# mLRS-tx-dualE22-top-v031.net
KiCad netlist of a schematic drawn in EAGLE
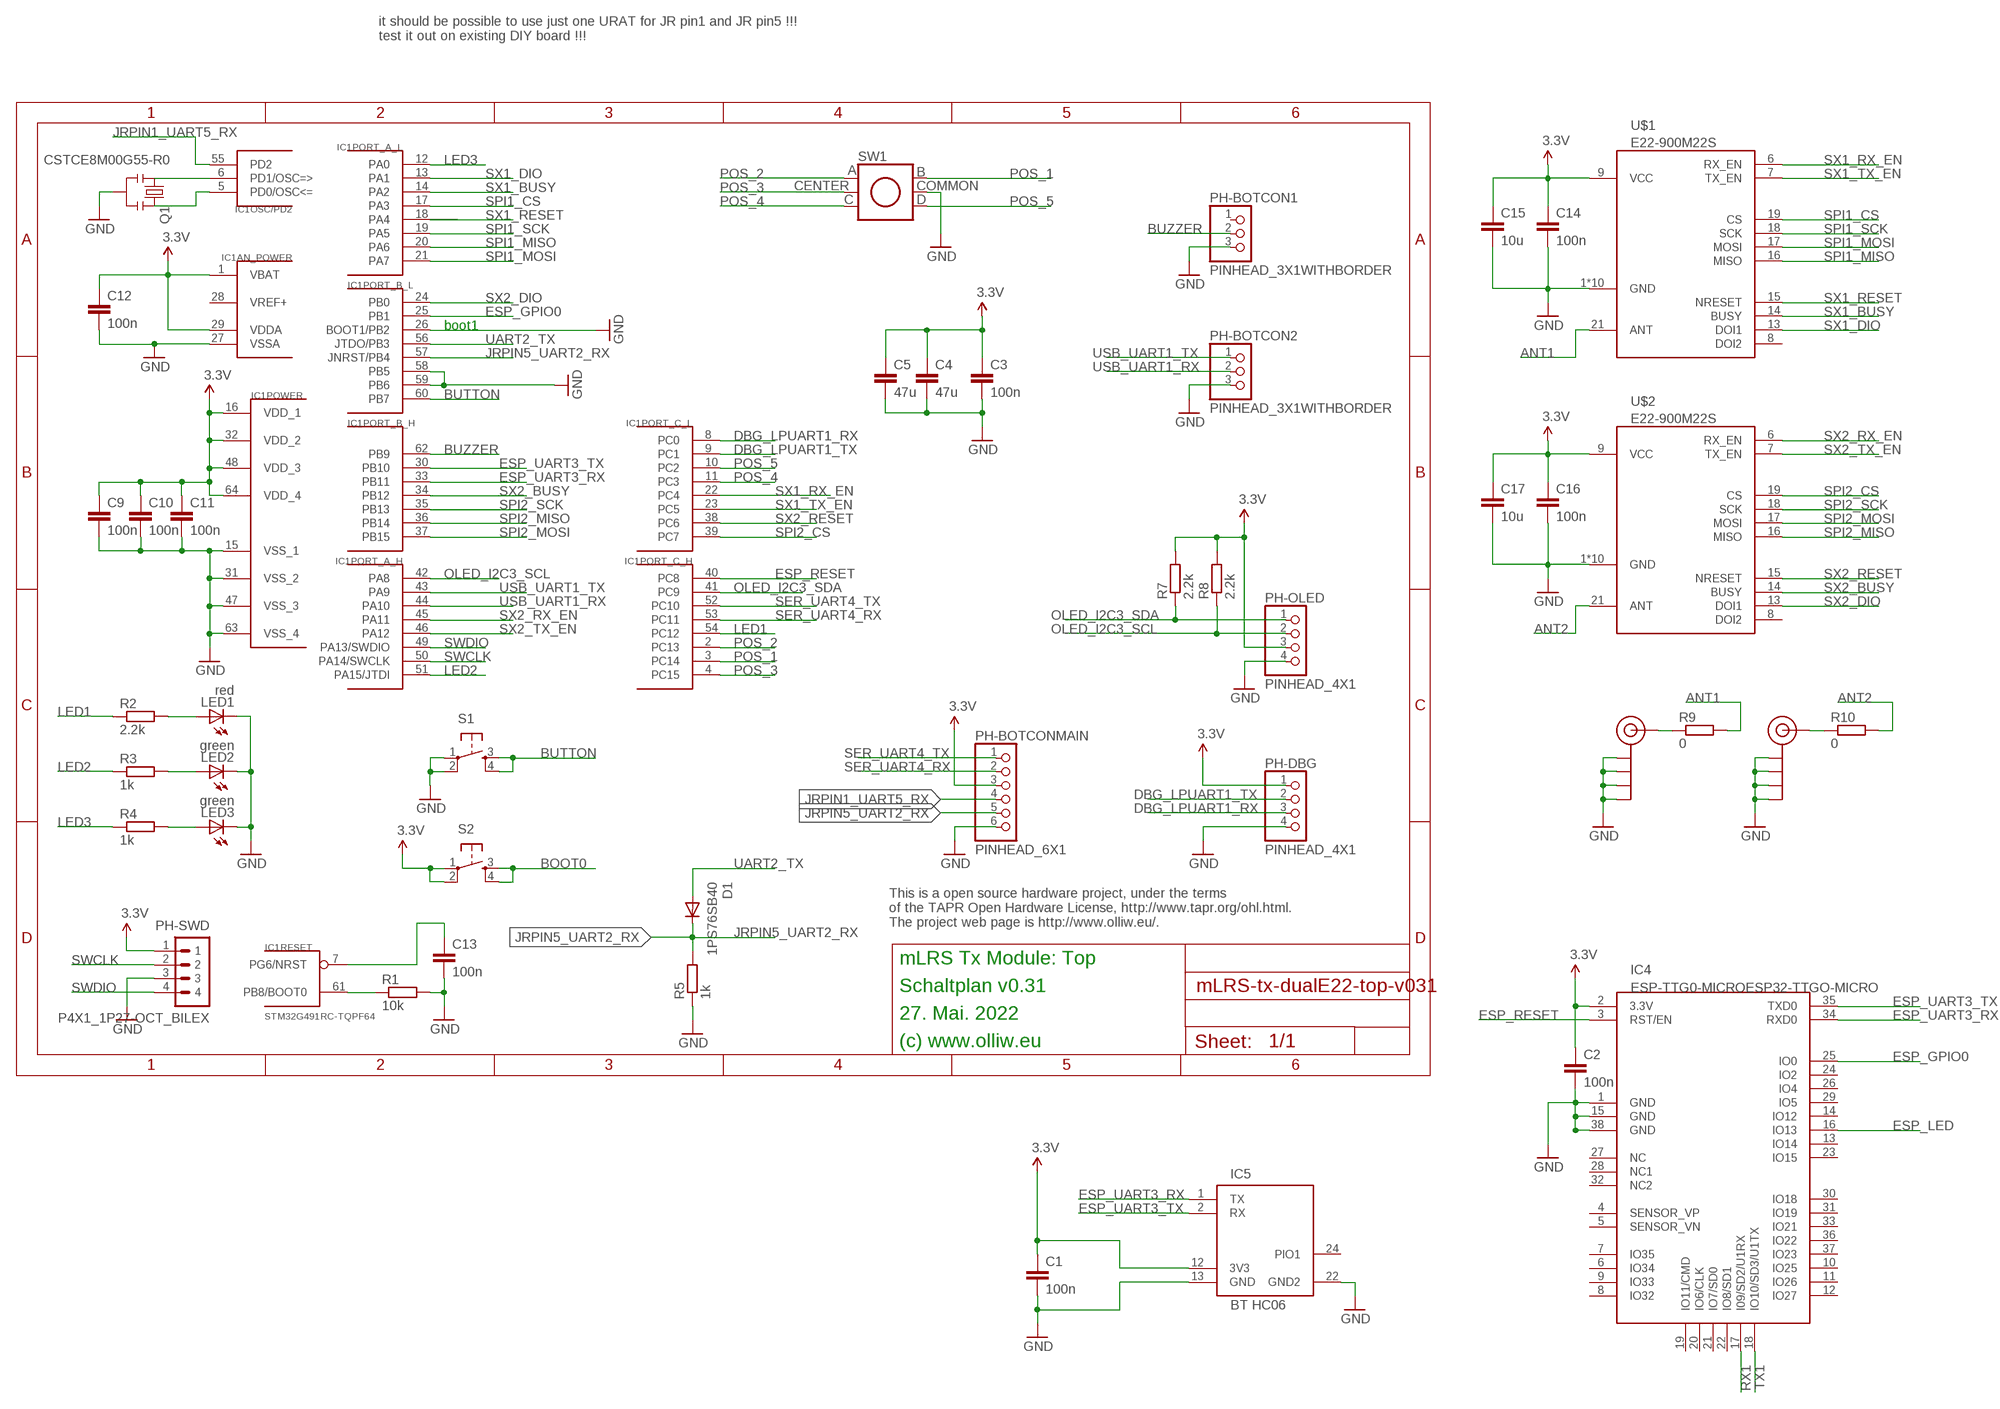
[diagram p0: schematic, sheet 1]

(export (version "E")
  (design (tool "Eeschema 10.0.6"))
  (components
    (comp (ref "C1")
      (value "100n")
      (footprint "eagle-import:C0603")
      (libsource (lib "eagle-import") (part "C-EUC0603"))
    )
    (comp (ref "C2")
      (value "100n")
      (footprint "eagle-import:C0603")
      (libsource (lib "eagle-import") (part "C-EUC0603"))
    )
    (comp (ref "C3")
      (value "100n")
      (footprint "eagle-import:C0402")
      (libsource (lib "eagle-import") (part "C-EUC0402"))
    )
    (comp (ref "C4")
      (value "47u")
      (footprint "eagle-import:C1210")
      (libsource (lib "eagle-import") (part "C-EUC1210"))
    )
    (comp (ref "C5")
      (value "47u")
      (footprint "eagle-import:C1206K")
      (libsource (lib "eagle-import") (part "C-EUC1206K"))
    )
    (comp (ref "C9")
      (value "100n")
      (footprint "eagle-import:C0402")
      (libsource (lib "eagle-import") (part "C-EUC0402"))
    )
    (comp (ref "C10")
      (value "100n")
      (footprint "eagle-import:C0402")
      (libsource (lib "eagle-import") (part "C-EUC0402"))
    )
    (comp (ref "C11")
      (value "100n")
      (footprint "eagle-import:C0402")
      (libsource (lib "eagle-import") (part "C-EUC0402"))
    )
    (comp (ref "C12")
      (value "100n")
      (footprint "eagle-import:C0402")
      (libsource (lib "eagle-import") (part "C-EUC0402"))
    )
    (comp (ref "C13")
      (value "100n")
      (footprint "eagle-import:C0402")
      (libsource (lib "eagle-import") (part "C-EUC0402"))
    )
    (comp (ref "C14")
      (value "100n")
      (footprint "eagle-import:C0402")
      (libsource (lib "eagle-import") (part "C-EUC0402"))
    )
    (comp (ref "C15")
      (value "10u")
      (footprint "eagle-import:C0603")
      (libsource (lib "eagle-import") (part "C-EUC0603"))
    )
    (comp (ref "C16")
      (value "100n")
      (footprint "eagle-import:C0402")
      (libsource (lib "eagle-import") (part "C-EUC0402"))
    )
    (comp (ref "C17")
      (value "10u")
      (footprint "eagle-import:C0603")
      (libsource (lib "eagle-import") (part "C-EUC0603"))
    )
    (comp (ref "D1")
      (value "1PS76SB40")
      (footprint "eagle-import:SOD110-R")
      (libsource (lib "eagle-import") (part "DIODE-SOD110-R"))
    )
    (comp (ref "IC1")
      (value "STM32G491RC-TQPF64")
      (footprint "eagle-import:TQFP64")
      (libsource (lib "eagle-import") (part "STM32G4X1RX-TQPF64"))
    )
    (comp (ref "IC4")
      (value "ESP-TTG0-MICROESP32-TTGO-MICRO")
      (footprint "eagle-import:ESP32-TTGO-MICRO")
      (libsource (lib "eagle-import") (part "ESP-TTG0-MICROESP32-TTGO-MICRO"))
    )
    (comp (ref "IC5")
      (value "BT HC06")
      (footprint "eagle-import:BT_HC05_BASIC")
      (libsource (lib "eagle-import") (part "HC06-BASIC"))
    )
    (comp (ref "LED1")
      (value "red")
      (footprint "eagle-import:CHIPLED_0603")
      (libsource (lib "eagle-import") (part "LEDCHIPLED_0603"))
    )
    (comp (ref "LED2")
      (value "green")
      (footprint "eagle-import:CHIPLED_0603")
      (libsource (lib "eagle-import") (part "LEDCHIPLED_0603"))
    )
    (comp (ref "LED3")
      (value "green")
      (footprint "eagle-import:CHIPLED_0603")
      (libsource (lib "eagle-import") (part "LEDCHIPLED_0603"))
    )
    (comp (ref "PH-BOTCON1")
      (value "PINHEAD_3X1WITHBORDER")
      (footprint "eagle-import:PINHEAD_3X1")
      (libsource (lib "eagle-import") (part "PINHEAD_3X1WITHBORDER"))
    )
    (comp (ref "PH-BOTCON2")
      (value "PINHEAD_3X1WITHBORDER")
      (footprint "eagle-import:PINHEAD_3X1")
      (libsource (lib "eagle-import") (part "PINHEAD_3X1WITHBORDER"))
    )
    (comp (ref "PH-BOTCONMAIN")
      (value "PINHEAD_6X1")
      (footprint "eagle-import:PINHEAD_6X1")
      (libsource (lib "eagle-import") (part "PINHEAD_6X1"))
    )
    (comp (ref "PH-DBG")
      (value "PINHEAD_4X1")
      (footprint "eagle-import:PINHEAD_4X1")
      (libsource (lib "eagle-import") (part "PINHEAD_4X1"))
    )
    (comp (ref "PH-OLED")
      (value "PINHEAD_4X1")
      (footprint "eagle-import:PINHEAD_4X1")
      (libsource (lib "eagle-import") (part "PINHEAD_4X1"))
    )
    (comp (ref "PH-SWD")
      (value "P4X1_1P27-OCT_BILEX")
      (footprint "eagle-import:4X1_1P27_OCT_BILEX")
      (libsource (lib "eagle-import") (part "P4X1_1P27-OCT_BILEX"))
    )
    (comp (ref "Q1")
      (value "CSTCE8M00G55-R0")
      (footprint "eagle-import:RESONATOR-SMD")
      (libsource (lib "eagle-import") (part "RESONATORSMD"))
    )
    (comp (ref "R1")
      (value "10k")
      (footprint "eagle-import:R0402")
      (libsource (lib "eagle-import") (part "R-EU_R0402"))
    )
    (comp (ref "R2")
      (value "2.2k")
      (footprint "eagle-import:R0402")
      (libsource (lib "eagle-import") (part "R-EU_R0402"))
    )
    (comp (ref "R3")
      (value "1k")
      (footprint "eagle-import:R0402")
      (libsource (lib "eagle-import") (part "R-EU_R0402"))
    )
    (comp (ref "R4")
      (value "1k")
      (footprint "eagle-import:R0402")
      (libsource (lib "eagle-import") (part "R-EU_R0402"))
    )
    (comp (ref "R5")
      (value "1k")
      (footprint "eagle-import:R0402")
      (libsource (lib "eagle-import") (part "R-EU_R0402"))
    )
    (comp (ref "R7")
      (value "2.2k")
      (footprint "eagle-import:R0402")
      (libsource (lib "eagle-import") (part "R-EU_R0402"))
    )
    (comp (ref "R8")
      (value "2.2k")
      (footprint "eagle-import:R0402")
      (libsource (lib "eagle-import") (part "R-EU_R0402"))
    )
    (comp (ref "R9")
      (value "0")
      (footprint "eagle-import:R0402")
      (libsource (lib "eagle-import") (part "R-EU_R0402"))
    )
    (comp (ref "R10")
      (value "0")
      (footprint "eagle-import:R0402")
      (libsource (lib "eagle-import") (part "R-EU_R0402"))
    )
    (comp (ref "RF1")
      (value "SMA_EDGE")
      (footprint "eagle-import:SMA-EDGE")
      (libsource (lib "eagle-import") (part "SMA_EDGE"))
    )
    (comp (ref "RF2")
      (value "SMA_EDGE")
      (footprint "eagle-import:SMA-EDGE")
      (libsource (lib "eagle-import") (part "SMA_EDGE"))
    )
    (comp (ref "S1")
      (value "TAC_SWITCHPTH")
      (footprint "eagle-import:TACTILE-PTH")
      (libsource (lib "eagle-import") (part "TAC_SWITCHPTH"))
    )
    (comp (ref "S2")
      (value "TAC_SWITCHPTH")
      (footprint "eagle-import:TACTILE-PTH")
      (libsource (lib "eagle-import") (part "TAC_SWITCHPTH"))
    )
    (comp (ref "SW1")
      (value "JOYSTICK-5WAY")
      (footprint "eagle-import:JOYSTICK-5WAY")
      (libsource (lib "eagle-import") (part "JOYSTICK-5WAY"))
    )
    (comp (ref "U$1")
      (value "E22-900M22S")
      (footprint "eagle-import:E22-900M22S")
      (libsource (lib "eagle-import") (part "E22-900M22S"))
    )
    (comp (ref "U$2")
      (value "E22-900M22S")
      (footprint "eagle-import:E22-900M22S")
      (libsource (lib "eagle-import") (part "E22-900M22S"))
    )
  )
  (nets
    (net (code "1") (name "/ANT1") (class "Default")
      (node (ref "R9") (pin "2") (pinfunction "2_2") (pintype "passive"))
      (node (ref "U$1") (pin "21") (pinfunction "ANT_21") (pintype "bidirectional"))
    )
    (net (code "2") (name "/ANT2") (class "Default")
      (node (ref "R10") (pin "2") (pinfunction "2_2") (pintype "passive"))
      (node (ref "U$2") (pin "21") (pinfunction "ANT_21") (pintype "bidirectional"))
    )
    (net (code "3") (name "/BOOT0") (class "Default")
      (node (ref "IC1") (pin "61") (pinfunction "PB8/BOOT0_61") (pintype "input"))
      (node (ref "R1") (pin "1") (pinfunction "1_1") (pintype "passive"))
      (node (ref "S2") (pin "3") (pinfunction "3_3") (pintype "passive"))
      (node (ref "S2") (pin "4") (pinfunction "4_4") (pintype "passive"))
    )
    (net (code "4") (name "/BUTTON") (class "Default")
      (node (ref "IC1") (pin "60") (pinfunction "PB7_60") (pintype "bidirectional"))
      (node (ref "S1") (pin "3") (pinfunction "3_3") (pintype "passive"))
      (node (ref "S1") (pin "4") (pinfunction "4_4") (pintype "passive"))
    )
    (net (code "5") (name "/BUZZER") (class "Default")
      (node (ref "IC1") (pin "62") (pinfunction "PB9_62") (pintype "bidirectional"))
      (node (ref "PH-BOTCON1") (pin "2") (pinfunction "3_2") (pintype "passive"))
    )
    (net (code "6") (name "/DBG_LPUART1_RX") (class "Default")
      (node (ref "IC1") (pin "8") (pinfunction "PC0_8") (pintype "bidirectional"))
      (node (ref "PH-DBG") (pin "3") (pinfunction "3_3") (pintype "passive"))
    )
    (net (code "7") (name "/DBG_LPUART1_TX") (class "Default")
      (node (ref "IC1") (pin "9") (pinfunction "PC1_9") (pintype "bidirectional"))
      (node (ref "PH-DBG") (pin "2") (pinfunction "2_2") (pintype "passive"))
    )
    (net (code "8") (name "/ESP_GPIO0") (class "Default")
      (node (ref "IC1") (pin "25") (pinfunction "PB1_25") (pintype "bidirectional"))
      (node (ref "IC4") (pin "25") (pinfunction "IO0_25") (pintype "bidirectional"))
    )
    (net (code "9") (name "/ESP_LED") (class "Default")
      (node (ref "IC4") (pin "16") (pinfunction "IO13_16") (pintype "bidirectional"))
    )
    (net (code "10") (name "/ESP_RESET") (class "Default")
      (node (ref "IC1") (pin "40") (pinfunction "PC8_40") (pintype "bidirectional"))
      (node (ref "IC4") (pin "3") (pinfunction "RST/EN_3") (pintype "input"))
    )
    (net (code "11") (name "/ESP_UART3_RX") (class "Default")
      (node (ref "IC1") (pin "33") (pinfunction "PB11_33") (pintype "bidirectional"))
      (node (ref "IC4") (pin "34") (pinfunction "RXD0_34") (pintype "bidirectional"))
      (node (ref "IC5") (pin "1") (pinfunction "TX_1") (pintype "bidirectional"))
    )
    (net (code "12") (name "/ESP_UART3_TX") (class "Default")
      (node (ref "IC1") (pin "30") (pinfunction "PB10_30") (pintype "bidirectional"))
      (node (ref "IC4") (pin "35") (pinfunction "TXD0_35") (pintype "bidirectional"))
      (node (ref "IC5") (pin "2") (pinfunction "RX_2") (pintype "bidirectional"))
    )
    (net (code "13") (name "/LED1") (class "Default")
      (node (ref "IC1") (pin "54") (pinfunction "PC12_54") (pintype "bidirectional"))
      (node (ref "R2") (pin "1") (pinfunction "1_1") (pintype "passive"))
    )
    (net (code "14") (name "/LED2") (class "Default")
      (node (ref "IC1") (pin "51") (pinfunction "PA15/JTDI_51") (pintype "bidirectional"))
      (node (ref "R3") (pin "1") (pinfunction "1_1") (pintype "passive"))
    )
    (net (code "15") (name "/LED3") (class "Default")
      (node (ref "IC1") (pin "12") (pinfunction "PA0_12") (pintype "bidirectional"))
      (node (ref "R4") (pin "1") (pinfunction "1_1") (pintype "passive"))
    )
    (net (code "16") (name "/OLED_I2C3_SCL") (class "Default")
      (node (ref "IC1") (pin "42") (pinfunction "PA8_42") (pintype "bidirectional"))
      (node (ref "PH-OLED") (pin "2") (pinfunction "2_2") (pintype "passive"))
      (node (ref "R8") (pin "1") (pinfunction "1_1") (pintype "passive"))
    )
    (net (code "17") (name "/OLED_I2C3_SDA") (class "Default")
      (node (ref "IC1") (pin "41") (pinfunction "PC9_41") (pintype "bidirectional"))
      (node (ref "PH-OLED") (pin "1") (pinfunction "1_1") (pintype "passive"))
      (node (ref "R7") (pin "1") (pinfunction "1_1") (pintype "passive"))
    )
    (net (code "18") (name "/POS_1") (class "Default")
      (node (ref "IC1") (pin "3") (pinfunction "PC14_3") (pintype "bidirectional"))
      (node (ref "SW1") (pin "4") (pinfunction "B_4") (pintype "bidirectional"))
    )
    (net (code "19") (name "/POS_2") (class "Default")
      (node (ref "IC1") (pin "2") (pinfunction "PC13_2") (pintype "bidirectional"))
      (node (ref "SW1") (pin "1") (pinfunction "A_1") (pintype "bidirectional"))
    )
    (net (code "20") (name "/POS_3") (class "Default")
      (node (ref "IC1") (pin "4") (pinfunction "PC15_4") (pintype "bidirectional"))
      (node (ref "SW1") (pin "2") (pinfunction "CENTER_2") (pintype "bidirectional"))
    )
    (net (code "21") (name "/POS_4") (class "Default")
      (node (ref "IC1") (pin "11") (pinfunction "PC3_11") (pintype "bidirectional"))
      (node (ref "SW1") (pin "3") (pinfunction "C_3") (pintype "bidirectional"))
    )
    (net (code "22") (name "/POS_5") (class "Default")
      (node (ref "IC1") (pin "10") (pinfunction "PC2_10") (pintype "bidirectional"))
      (node (ref "SW1") (pin "6") (pinfunction "D_6") (pintype "bidirectional"))
    )
    (net (code "23") (name "/RX1") (class "Default")
      (node (ref "IC4") (pin "17") (pinfunction "I09/SD2/U1RX_17") (pintype "bidirectional"))
    )
    (net (code "24") (name "/SER_UART4_RX") (class "Default")
      (node (ref "IC1") (pin "53") (pinfunction "PC11_53") (pintype "bidirectional"))
      (node (ref "PH-BOTCONMAIN") (pin "2") (pinfunction "2_2") (pintype "passive"))
    )
    (net (code "25") (name "/SER_UART4_TX") (class "Default")
      (node (ref "IC1") (pin "52") (pinfunction "PC10_52") (pintype "bidirectional"))
      (node (ref "PH-BOTCONMAIN") (pin "1") (pinfunction "1_1") (pintype "passive"))
    )
    (net (code "26") (name "/SPI1_CS") (class "Default")
      (node (ref "IC1") (pin "17") (pinfunction "PA3_17") (pintype "bidirectional"))
      (node (ref "U$1") (pin "19") (pinfunction "CS_19") (pintype "bidirectional"))
    )
    (net (code "27") (name "/SPI1_MISO") (class "Default")
      (node (ref "IC1") (pin "20") (pinfunction "PA6_20") (pintype "bidirectional"))
      (node (ref "U$1") (pin "16") (pinfunction "MISO_16") (pintype "bidirectional"))
    )
    (net (code "28") (name "/SPI1_MOSI") (class "Default")
      (node (ref "IC1") (pin "21") (pinfunction "PA7_21") (pintype "bidirectional"))
      (node (ref "U$1") (pin "17") (pinfunction "MOSI_17") (pintype "bidirectional"))
    )
    (net (code "29") (name "/SPI1_SCK") (class "Default")
      (node (ref "IC1") (pin "19") (pinfunction "PA5_19") (pintype "bidirectional"))
      (node (ref "U$1") (pin "18") (pinfunction "SCK_18") (pintype "bidirectional"))
    )
    (net (code "30") (name "/SPI2_CS") (class "Default")
      (node (ref "IC1") (pin "39") (pinfunction "PC7_39") (pintype "bidirectional"))
      (node (ref "U$2") (pin "19") (pinfunction "CS_19") (pintype "bidirectional"))
    )
    (net (code "31") (name "/SPI2_MISO") (class "Default")
      (node (ref "IC1") (pin "36") (pinfunction "PB14_36") (pintype "bidirectional"))
      (node (ref "U$2") (pin "16") (pinfunction "MISO_16") (pintype "bidirectional"))
    )
    (net (code "32") (name "/SPI2_MOSI") (class "Default")
      (node (ref "IC1") (pin "37") (pinfunction "PB15_37") (pintype "bidirectional"))
      (node (ref "U$2") (pin "17") (pinfunction "MOSI_17") (pintype "bidirectional"))
    )
    (net (code "33") (name "/SPI2_SCK") (class "Default")
      (node (ref "IC1") (pin "35") (pinfunction "PB13_35") (pintype "bidirectional"))
      (node (ref "U$2") (pin "18") (pinfunction "SCK_18") (pintype "bidirectional"))
    )
    (net (code "34") (name "/SWCLK") (class "Default")
      (node (ref "IC1") (pin "50") (pinfunction "PA14/SWCLK_50") (pintype "bidirectional"))
      (node (ref "PH-SWD") (pin "2") (pinfunction "2_2") (pintype "passive"))
    )
    (net (code "35") (name "/SWDIO") (class "Default")
      (node (ref "IC1") (pin "49") (pinfunction "PA13/SWDIO_49") (pintype "bidirectional"))
      (node (ref "PH-SWD") (pin "4") (pinfunction "4_4") (pintype "passive"))
    )
    (net (code "36") (name "/SX1_BUSY") (class "Default")
      (node (ref "IC1") (pin "14") (pinfunction "PA2_14") (pintype "bidirectional"))
      (node (ref "U$1") (pin "14") (pinfunction "BUSY_14") (pintype "bidirectional"))
    )
    (net (code "37") (name "/SX1_DIO") (class "Default")
      (node (ref "IC1") (pin "13") (pinfunction "PA1_13") (pintype "bidirectional"))
      (node (ref "U$1") (pin "13") (pinfunction "DOI1_13") (pintype "bidirectional"))
    )
    (net (code "38") (name "/SX1_RESET") (class "Default")
      (node (ref "IC1") (pin "18") (pinfunction "PA4_18") (pintype "bidirectional"))
      (node (ref "U$1") (pin "15") (pinfunction "NRESET_15") (pintype "input"))
    )
    (net (code "39") (name "/SX1_RX_EN") (class "Default")
      (node (ref "IC1") (pin "22") (pinfunction "PC4_22") (pintype "bidirectional"))
      (node (ref "U$1") (pin "6") (pinfunction "RX_EN_6") (pintype "bidirectional"))
    )
    (net (code "40") (name "/SX1_TX_EN") (class "Default")
      (node (ref "IC1") (pin "23") (pinfunction "PC5_23") (pintype "bidirectional"))
      (node (ref "U$1") (pin "7") (pinfunction "TX_EN_7") (pintype "bidirectional"))
    )
    (net (code "41") (name "/SX2_BUSY") (class "Default")
      (node (ref "IC1") (pin "34") (pinfunction "PB12_34") (pintype "bidirectional"))
      (node (ref "U$2") (pin "14") (pinfunction "BUSY_14") (pintype "bidirectional"))
    )
    (net (code "42") (name "/SX2_DIO") (class "Default")
      (node (ref "IC1") (pin "24") (pinfunction "PB0_24") (pintype "bidirectional"))
      (node (ref "U$2") (pin "13") (pinfunction "DOI1_13") (pintype "bidirectional"))
    )
    (net (code "43") (name "/SX2_RESET") (class "Default")
      (node (ref "IC1") (pin "38") (pinfunction "PC6_38") (pintype "bidirectional"))
      (node (ref "U$2") (pin "15") (pinfunction "NRESET_15") (pintype "input"))
    )
    (net (code "44") (name "/SX2_RX_EN") (class "Default")
      (node (ref "IC1") (pin "45") (pinfunction "PA11_45") (pintype "bidirectional"))
      (node (ref "U$2") (pin "6") (pinfunction "RX_EN_6") (pintype "bidirectional"))
    )
    (net (code "45") (name "/SX2_TX_EN") (class "Default")
      (node (ref "IC1") (pin "46") (pinfunction "PA12_46") (pintype "bidirectional"))
      (node (ref "U$2") (pin "7") (pinfunction "TX_EN_7") (pintype "bidirectional"))
    )
    (net (code "46") (name "/TX1") (class "Default")
      (node (ref "IC4") (pin "18") (pinfunction "IO10/SD3/U1TX_18") (pintype "bidirectional"))
    )
    (net (code "47") (name "/UART2_TX") (class "Default")
      (node (ref "D1") (pin "A") (pinfunction "A_A") (pintype "passive"))
      (node (ref "IC1") (pin "56") (pinfunction "JTDO/PB3_56") (pintype "bidirectional"))
    )
    (net (code "48") (name "/USB_UART1_RX") (class "Default")
      (node (ref "IC1") (pin "44") (pinfunction "PA10_44") (pintype "bidirectional"))
      (node (ref "PH-BOTCON2") (pin "2") (pinfunction "3_2") (pintype "passive"))
    )
    (net (code "49") (name "/USB_UART1_TX") (class "Default")
      (node (ref "IC1") (pin "43") (pinfunction "PA9_43") (pintype "bidirectional"))
      (node (ref "PH-BOTCON2") (pin "1") (pinfunction "1_1") (pintype "passive"))
    )
    (net (code "50") (name "3.3V") (class "Default")
      (node (ref "C1") (pin "1") (pinfunction "1_1") (pintype "passive"))
      (node (ref "C10") (pin "1") (pinfunction "1_1") (pintype "passive"))
      (node (ref "C11") (pin "1") (pinfunction "1_1") (pintype "passive"))
      (node (ref "C12") (pin "1") (pinfunction "1_1") (pintype "passive"))
      (node (ref "C14") (pin "1") (pinfunction "1_1") (pintype "passive"))
      (node (ref "C15") (pin "1") (pinfunction "1_1") (pintype "passive"))
      (node (ref "C16") (pin "1") (pinfunction "1_1") (pintype "passive"))
      (node (ref "C17") (pin "1") (pinfunction "1_1") (pintype "passive"))
      (node (ref "C2") (pin "1") (pinfunction "1_1") (pintype "passive"))
      (node (ref "C3") (pin "1") (pinfunction "1_1") (pintype "passive"))
      (node (ref "C4") (pin "1") (pinfunction "1_1") (pintype "passive"))
      (node (ref "C5") (pin "1") (pinfunction "1_1") (pintype "passive"))
      (node (ref "C9") (pin "1") (pinfunction "1_1") (pintype "passive"))
      (node (ref "IC1") (pin "1") (pinfunction "VBAT_1") (pintype "power_in"))
      (node (ref "IC1") (pin "16") (pinfunction "VDD_1_16") (pintype "power_in"))
      (node (ref "IC1") (pin "29") (pinfunction "VDDA_29") (pintype "power_in"))
      (node (ref "IC1") (pin "32") (pinfunction "VDD_2_32") (pintype "power_in"))
      (node (ref "IC1") (pin "48") (pinfunction "VDD_3_48") (pintype "power_in"))
      (node (ref "IC1") (pin "64") (pinfunction "VDD_4_64") (pintype "power_in"))
      (node (ref "IC4") (pin "2") (pinfunction "3.3V_2") (pintype "power_in"))
      (node (ref "IC5") (pin "12") (pinfunction "3V3_12") (pintype "bidirectional"))
      (node (ref "PH-BOTCONMAIN") (pin "3") (pinfunction "3_3") (pintype "passive"))
      (node (ref "PH-DBG") (pin "1") (pinfunction "1_1") (pintype "passive"))
      (node (ref "PH-OLED") (pin "3") (pinfunction "3_3") (pintype "passive"))
      (node (ref "PH-SWD") (pin "1") (pinfunction "1_1") (pintype "passive"))
      (node (ref "R7") (pin "2") (pinfunction "2_2") (pintype "passive"))
      (node (ref "R8") (pin "2") (pinfunction "2_2") (pintype "passive"))
      (node (ref "S2") (pin "1") (pinfunction "1_1") (pintype "passive"))
      (node (ref "S2") (pin "2") (pinfunction "2_2") (pintype "passive"))
      (node (ref "U$1") (pin "9") (pinfunction "VCC_9") (pintype "power_in"))
      (node (ref "U$2") (pin "9") (pinfunction "VCC_9") (pintype "power_in"))
    )
    (net (code "51") (name "GND") (class "Default")
      (node (ref "C1") (pin "2") (pinfunction "2_2") (pintype "passive"))
      (node (ref "C10") (pin "2") (pinfunction "2_2") (pintype "passive"))
      (node (ref "C11") (pin "2") (pinfunction "2_2") (pintype "passive"))
      (node (ref "C12") (pin "2") (pinfunction "2_2") (pintype "passive"))
      (node (ref "C13") (pin "2") (pinfunction "2_2") (pintype "passive"))
      (node (ref "C14") (pin "2") (pinfunction "2_2") (pintype "passive"))
      (node (ref "C15") (pin "2") (pinfunction "2_2") (pintype "passive"))
      (node (ref "C16") (pin "2") (pinfunction "2_2") (pintype "passive"))
      (node (ref "C17") (pin "2") (pinfunction "2_2") (pintype "passive"))
      (node (ref "C2") (pin "2") (pinfunction "2_2") (pintype "passive"))
      (node (ref "C3") (pin "2") (pinfunction "2_2") (pintype "passive"))
      (node (ref "C4") (pin "2") (pinfunction "2_2") (pintype "passive"))
      (node (ref "C5") (pin "2") (pinfunction "2_2") (pintype "passive"))
      (node (ref "C9") (pin "2") (pinfunction "2_2") (pintype "passive"))
      (node (ref "IC1") (pin "15") (pinfunction "VSS_1_15") (pintype "power_in"))
      (node (ref "IC1") (pin "26") (pinfunction "BOOT1/PB2_26") (pintype "bidirectional"))
      (node (ref "IC1") (pin "27") (pinfunction "VSSA_27") (pintype "power_in"))
      (node (ref "IC1") (pin "31") (pinfunction "VSS_2_31") (pintype "power_in"))
      (node (ref "IC1") (pin "47") (pinfunction "VSS_3_47") (pintype "power_in"))
      (node (ref "IC1") (pin "58") (pinfunction "PB5_58") (pintype "bidirectional"))
      (node (ref "IC1") (pin "59") (pinfunction "PB6_59") (pintype "bidirectional"))
      (node (ref "IC1") (pin "63") (pinfunction "VSS_4_63") (pintype "power_in"))
      (node (ref "IC4") (pin "1") (pinfunction "GND_1") (pintype "power_in"))
      (node (ref "IC4") (pin "15") (pinfunction "GND_15") (pintype "power_in"))
      (node (ref "IC4") (pin "38") (pinfunction "GND_38") (pintype "power_in"))
      (node (ref "IC5") (pin "13") (pinfunction "GND_13") (pintype "bidirectional"))
      (node (ref "IC5") (pin "22") (pinfunction "GND2_22") (pintype "bidirectional"))
      (node (ref "LED1") (pin "C") (pinfunction "C_C") (pintype "passive"))
      (node (ref "LED2") (pin "C") (pinfunction "C_C") (pintype "passive"))
      (node (ref "LED3") (pin "C") (pinfunction "C_C") (pintype "passive"))
      (node (ref "PH-BOTCON1") (pin "3") (pinfunction "5_3") (pintype "passive"))
      (node (ref "PH-BOTCON2") (pin "3") (pinfunction "5_3") (pintype "passive"))
      (node (ref "PH-BOTCONMAIN") (pin "6") (pinfunction "6_6") (pintype "passive"))
      (node (ref "PH-DBG") (pin "4") (pinfunction "4_4") (pintype "passive"))
      (node (ref "PH-OLED") (pin "4") (pinfunction "4_4") (pintype "passive"))
      (node (ref "PH-SWD") (pin "3") (pinfunction "3_3") (pintype "passive"))
      (node (ref "Q1") (pin "2") (pinfunction "2_2") (pintype "passive"))
      (node (ref "R1") (pin "2") (pinfunction "2_2") (pintype "passive"))
      (node (ref "R5") (pin "1") (pinfunction "1_1") (pintype "passive"))
      (node (ref "RF1") (pin "GND@0") (pinfunction "GND_GND@0") (pintype "bidirectional"))
      (node (ref "RF1") (pin "GND@1") (pinfunction "GND_GND@1") (pintype "bidirectional"))
      (node (ref "RF1") (pin "GND@2") (pinfunction "GND_GND@2") (pintype "bidirectional"))
      (node (ref "RF1") (pin "GND@3") (pinfunction "GND_GND@3") (pintype "bidirectional"))
      (node (ref "RF2") (pin "GND@0") (pinfunction "GND_GND@0") (pintype "bidirectional"))
      (node (ref "RF2") (pin "GND@1") (pinfunction "GND_GND@1") (pintype "bidirectional"))
      (node (ref "RF2") (pin "GND@2") (pinfunction "GND_GND@2") (pintype "bidirectional"))
      (node (ref "RF2") (pin "GND@3") (pinfunction "GND_GND@3") (pintype "bidirectional"))
      (node (ref "S1") (pin "1") (pinfunction "1_1") (pintype "passive"))
      (node (ref "S1") (pin "2") (pinfunction "2_2") (pintype "passive"))
      (node (ref "SW1") (pin "5") (pinfunction "COMMON_5") (pintype "bidirectional"))
      (node (ref "U$1") (pin "1") (pinfunction "GND_1") (pintype "power_in"))
      (node (ref "U$1") (pin "10") (pinfunction "GND_10") (pintype "power_in"))
      (node (ref "U$1") (pin "11") (pinfunction "GND_11") (pintype "power_in"))
      (node (ref "U$1") (pin "12") (pinfunction "GND_12") (pintype "power_in"))
      (node (ref "U$1") (pin "2") (pinfunction "GND_2") (pintype "power_in"))
      (node (ref "U$1") (pin "20") (pinfunction "GND_20") (pintype "power_in"))
      (node (ref "U$1") (pin "22") (pinfunction "GND_22") (pintype "power_in"))
      (node (ref "U$1") (pin "3") (pinfunction "GND_3") (pintype "power_in"))
      (node (ref "U$1") (pin "4") (pinfunction "GND_4") (pintype "power_in"))
      (node (ref "U$1") (pin "5") (pinfunction "GND_5") (pintype "power_in"))
      (node (ref "U$2") (pin "1") (pinfunction "GND_1") (pintype "power_in"))
      (node (ref "U$2") (pin "10") (pinfunction "GND_10") (pintype "power_in"))
      (node (ref "U$2") (pin "11") (pinfunction "GND_11") (pintype "power_in"))
      (node (ref "U$2") (pin "12") (pinfunction "GND_12") (pintype "power_in"))
      (node (ref "U$2") (pin "2") (pinfunction "GND_2") (pintype "power_in"))
      (node (ref "U$2") (pin "20") (pinfunction "GND_20") (pintype "power_in"))
      (node (ref "U$2") (pin "22") (pinfunction "GND_22") (pintype "power_in"))
      (node (ref "U$2") (pin "3") (pinfunction "GND_3") (pintype "power_in"))
      (node (ref "U$2") (pin "4") (pinfunction "GND_4") (pintype "power_in"))
      (node (ref "U$2") (pin "5") (pinfunction "GND_5") (pintype "power_in"))
    )
    (net (code "52") (name "JRPIN1_UART5_RX") (class "Default")
      (node (ref "IC1") (pin "55") (pinfunction "PD2_55") (pintype "bidirectional"))
      (node (ref "PH-BOTCONMAIN") (pin "4") (pinfunction "4_4") (pintype "passive"))
    )
    (net (code "53") (name "JRPIN5_UART2_RX") (class "Default")
      (node (ref "D1") (pin "C") (pinfunction "C_C") (pintype "passive"))
      (node (ref "IC1") (pin "57") (pinfunction "JNRST/PB4_57") (pintype "bidirectional"))
      (node (ref "PH-BOTCONMAIN") (pin "5") (pinfunction "5_5") (pintype "passive"))
      (node (ref "R5") (pin "2") (pinfunction "2_2") (pintype "passive"))
    )
    (net (code "54") (name "Net-(IC1B-PD0{slash}OSC<=)") (class "Default")
      (node (ref "IC1") (pin "5") (pinfunction "PD0/OSC<=_5") (pintype "bidirectional"))
      (node (ref "Q1") (pin "3") (pinfunction "3_3") (pintype "passive"))
    )
    (net (code "55") (name "Net-(IC1B-PD1{slash}OSC=>)") (class "Default")
      (node (ref "IC1") (pin "6") (pinfunction "PD1/OSC=>_6") (pintype "bidirectional"))
      (node (ref "Q1") (pin "1") (pinfunction "1_1") (pintype "passive"))
    )
    (net (code "56") (name "Net-(IC1J-PG6{slash}NRST)") (class "Default")
      (node (ref "C13") (pin "1") (pinfunction "1_1") (pintype "passive"))
      (node (ref "IC1") (pin "7") (pinfunction "PG6/NRST_7") (pintype "input"))
    )
    (net (code "57") (name "Net-(LED1-PadA)") (class "Default")
      (node (ref "LED1") (pin "A") (pinfunction "A_A") (pintype "passive"))
      (node (ref "R2") (pin "2") (pinfunction "2_2") (pintype "passive"))
    )
    (net (code "58") (name "Net-(LED2-PadA)") (class "Default")
      (node (ref "LED2") (pin "A") (pinfunction "A_A") (pintype "passive"))
      (node (ref "R3") (pin "2") (pinfunction "2_2") (pintype "passive"))
    )
    (net (code "59") (name "Net-(LED3-PadA)") (class "Default")
      (node (ref "LED3") (pin "A") (pinfunction "A_A") (pintype "passive"))
      (node (ref "R4") (pin "2") (pinfunction "2_2") (pintype "passive"))
    )
    (net (code "60") (name "Net-(RF1-SIGNAL)") (class "Default")
      (node (ref "R9") (pin "1") (pinfunction "1_1") (pintype "passive"))
      (node (ref "RF1") (pin "SIG") (pinfunction "SIGNAL_SIG") (pintype "bidirectional"))
    )
    (net (code "61") (name "Net-(RF2-SIGNAL)") (class "Default")
      (node (ref "R10") (pin "1") (pinfunction "1_1") (pintype "passive"))
      (node (ref "RF2") (pin "SIG") (pinfunction "SIGNAL_SIG") (pintype "bidirectional"))
    )
    (net (code "62") (name "unconnected-(IC1A-VREF+-Pad28)") (class "Default")
      (node (ref "IC1") (pin "28") (pinfunction "VREF+_28") (pintype "input"))
    )
    (net (code "63") (name "unconnected-(IC4-IO2-Pad24)") (class "Default")
      (node (ref "IC4") (pin "24") (pinfunction "IO2_24") (pintype "bidirectional"))
    )
    (net (code "64") (name "unconnected-(IC4-IO4-Pad26)") (class "Default")
      (node (ref "IC4") (pin "26") (pinfunction "IO4_26") (pintype "bidirectional"))
    )
    (net (code "65") (name "unconnected-(IC4-IO5-Pad29)") (class "Default")
      (node (ref "IC4") (pin "29") (pinfunction "IO5_29") (pintype "bidirectional"))
    )
    (net (code "66") (name "unconnected-(IC4-IO6{slash}CLK-Pad20)") (class "Default")
      (node (ref "IC4") (pin "20") (pinfunction "IO6/CLK_20") (pintype "bidirectional"))
    )
    (net (code "67") (name "unconnected-(IC4-IO7{slash}SD0-Pad21)") (class "Default")
      (node (ref "IC4") (pin "21") (pinfunction "IO7/SD0_21") (pintype "bidirectional"))
    )
    (net (code "68") (name "unconnected-(IC4-IO8{slash}SD1-Pad22)") (class "Default")
      (node (ref "IC4") (pin "22") (pinfunction "IO8/SD1_22") (pintype "bidirectional"))
    )
    (net (code "69") (name "unconnected-(IC4-IO11{slash}CMD-Pad19)") (class "Default")
      (node (ref "IC4") (pin "19") (pinfunction "IO11/CMD_19") (pintype "bidirectional"))
    )
    (net (code "70") (name "unconnected-(IC4-IO12-Pad14)") (class "Default")
      (node (ref "IC4") (pin "14") (pinfunction "IO12_14") (pintype "bidirectional"))
    )
    (net (code "71") (name "unconnected-(IC4-IO14-Pad13)") (class "Default")
      (node (ref "IC4") (pin "13") (pinfunction "IO14_13") (pintype "bidirectional"))
    )
    (net (code "72") (name "unconnected-(IC4-IO15-Pad23)") (class "Default")
      (node (ref "IC4") (pin "23") (pinfunction "IO15_23") (pintype "bidirectional"))
    )
    (net (code "73") (name "unconnected-(IC4-IO18-Pad30)") (class "Default")
      (node (ref "IC4") (pin "30") (pinfunction "IO18_30") (pintype "bidirectional"))
    )
    (net (code "74") (name "unconnected-(IC4-IO19-Pad31)") (class "Default")
      (node (ref "IC4") (pin "31") (pinfunction "IO19_31") (pintype "bidirectional"))
    )
    (net (code "75") (name "unconnected-(IC4-IO21-Pad33)") (class "Default")
      (node (ref "IC4") (pin "33") (pinfunction "IO21_33") (pintype "bidirectional"))
    )
    (net (code "76") (name "unconnected-(IC4-IO22-Pad36)") (class "Default")
      (node (ref "IC4") (pin "36") (pinfunction "IO22_36") (pintype "bidirectional"))
    )
    (net (code "77") (name "unconnected-(IC4-IO23-Pad37)") (class "Default")
      (node (ref "IC4") (pin "37") (pinfunction "IO23_37") (pintype "bidirectional"))
    )
    (net (code "78") (name "unconnected-(IC4-IO25-Pad10)") (class "Default")
      (node (ref "IC4") (pin "10") (pinfunction "IO25_10") (pintype "bidirectional"))
    )
    (net (code "79") (name "unconnected-(IC4-IO26-Pad11)") (class "Default")
      (node (ref "IC4") (pin "11") (pinfunction "IO26_11") (pintype "bidirectional"))
    )
    (net (code "80") (name "unconnected-(IC4-IO27-Pad12)") (class "Default")
      (node (ref "IC4") (pin "12") (pinfunction "IO27_12") (pintype "bidirectional"))
    )
    (net (code "81") (name "unconnected-(IC4-IO32-Pad8)") (class "Default")
      (node (ref "IC4") (pin "8") (pinfunction "IO32_8") (pintype "bidirectional"))
    )
    (net (code "82") (name "unconnected-(IC4-IO33-Pad9)") (class "Default")
      (node (ref "IC4") (pin "9") (pinfunction "IO33_9") (pintype "bidirectional"))
    )
    (net (code "83") (name "unconnected-(IC4-IO34-Pad6)") (class "Default")
      (node (ref "IC4") (pin "6") (pinfunction "IO34_6") (pintype "bidirectional"))
    )
    (net (code "84") (name "unconnected-(IC4-IO35-Pad7)") (class "Default")
      (node (ref "IC4") (pin "7") (pinfunction "IO35_7") (pintype "bidirectional"))
    )
    (net (code "85") (name "unconnected-(IC4-NC-Pad27)") (class "Default")
      (node (ref "IC4") (pin "27") (pinfunction "NC_27") (pintype "no_connect"))
    )
    (net (code "86") (name "unconnected-(IC4-NC1-Pad28)") (class "Default")
      (node (ref "IC4") (pin "28") (pinfunction "NC1_28") (pintype "no_connect"))
    )
    (net (code "87") (name "unconnected-(IC4-NC2-Pad32)") (class "Default")
      (node (ref "IC4") (pin "32") (pinfunction "NC2_32") (pintype "no_connect"))
    )
    (net (code "88") (name "unconnected-(IC4-SENSOR_VN-Pad5)") (class "Default")
      (node (ref "IC4") (pin "5") (pinfunction "SENSOR_VN_5") (pintype "bidirectional"))
    )
    (net (code "89") (name "unconnected-(IC4-SENSOR_VP-Pad4)") (class "Default")
      (node (ref "IC4") (pin "4") (pinfunction "SENSOR_VP_4") (pintype "bidirectional"))
    )
    (net (code "90") (name "unconnected-(IC5-PIO1-Pad24)") (class "Default")
      (node (ref "IC5") (pin "24") (pinfunction "PIO1_24") (pintype "bidirectional"))
    )
    (net (code "91") (name "unconnected-(PH-BOTCON1-Pad1)") (class "Default")
      (node (ref "PH-BOTCON1") (pin "1") (pinfunction "1_1") (pintype "passive"))
    )
    (net (code "92") (name "unconnected-(U$1-DOI2-Pad8)") (class "Default")
      (node (ref "U$1") (pin "8") (pinfunction "DOI2_8") (pintype "bidirectional"))
    )
    (net (code "93") (name "unconnected-(U$2-DOI2-Pad8)") (class "Default")
      (node (ref "U$2") (pin "8") (pinfunction "DOI2_8") (pintype "bidirectional"))
    )
  )
)
